# V2164MIXER_v2.net
KiCad netlist of a schematic drawn in EAGLE
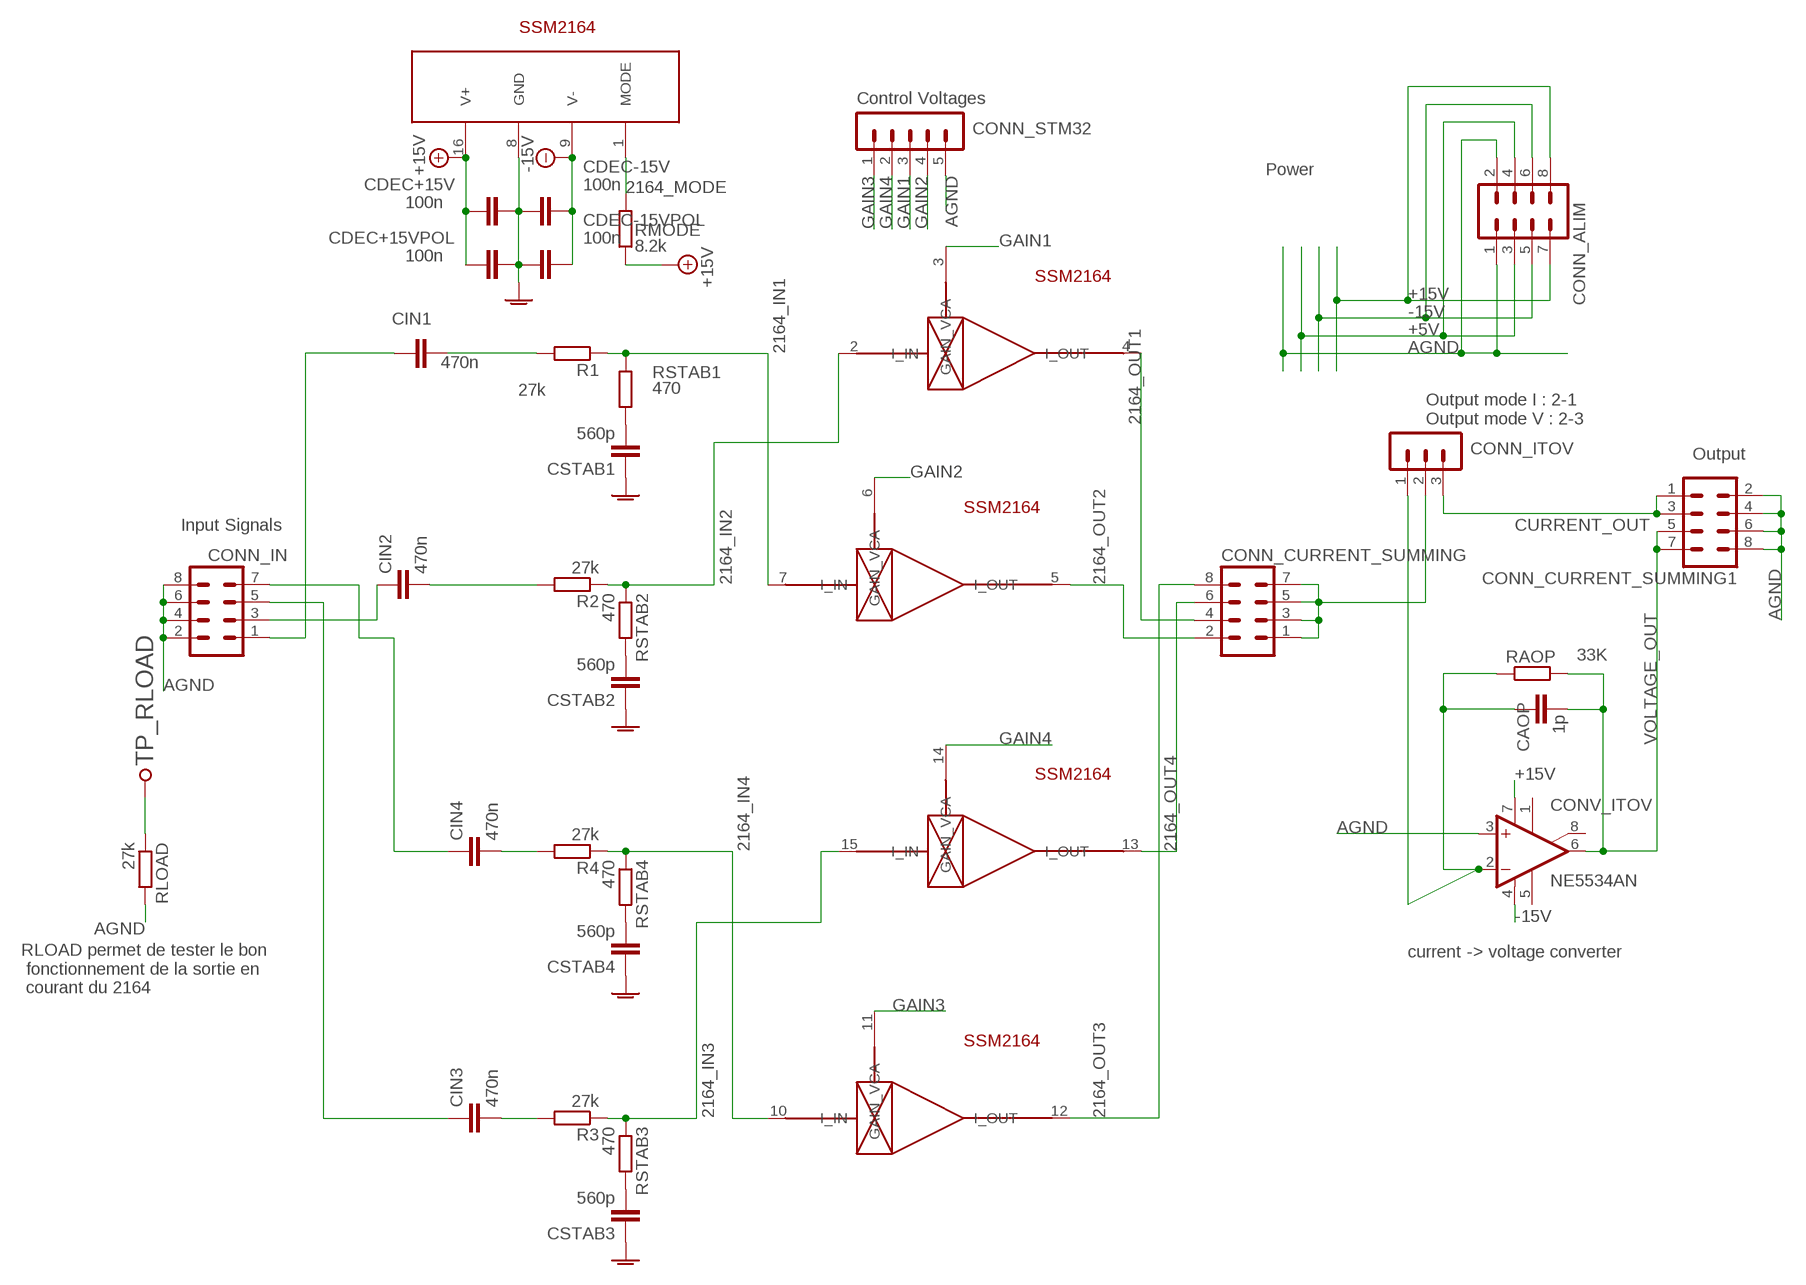
[diagram p0: schematic, sheet 1]

(export (version "E")
  (design (tool "Eeschema 10.0.6"))
  (components
    (comp (ref "CAOP")
      (value "1p")
      (footprint "eagle-import:C050-030X075")
      (fields (field (name "C3") "0.47 micro"))
      (libsource (lib "eagle-import") (part "C-EU050-030X075"))
    )
    (comp (ref "CDEC+15V")
      (value "100n")
      (footprint "eagle-import:C050-030X075")
      (libsource (lib "eagle-import") (part "C-EU050-030X075"))
    )
    (comp (ref "CDEC+15VPOL")
      (value "100n")
      (footprint "eagle-import:C075-032X103")
      (libsource (lib "eagle-import") (part "C-EU075-032X103"))
    )
    (comp (ref "CDEC-15V")
      (value "100n")
      (footprint "eagle-import:C050-030X075")
      (libsource (lib "eagle-import") (part "C-EU050-030X075"))
    )
    (comp (ref "CDEC-15VPOL")
      (value "100n")
      (footprint "eagle-import:C050-030X075")
      (libsource (lib "eagle-import") (part "C-EU050-030X075"))
    )
    (comp (ref "CIN1")
      (value "470n")
      (footprint "eagle-import:C050-030X075")
      (fields (field (name "C3") "0.47 micro"))
      (libsource (lib "eagle-import") (part "C-EU050-030X075"))
    )
    (comp (ref "CIN2")
      (value "470n")
      (footprint "eagle-import:C050-030X075")
      (fields (field (name "C3") "0.47 micro"))
      (libsource (lib "eagle-import") (part "C-EU050-030X075"))
    )
    (comp (ref "CIN3")
      (value "470n")
      (footprint "eagle-import:C050-030X075")
      (fields (field (name "C3") "0.47 micro"))
      (libsource (lib "eagle-import") (part "C-EU050-030X075"))
    )
    (comp (ref "CIN4")
      (value "470n")
      (footprint "eagle-import:C050-030X075")
      (fields (field (name "C3") "0.47 micro"))
      (libsource (lib "eagle-import") (part "C-EU050-030X075"))
    )
    (comp (ref "CONN_ALIM")
      (value "MA04-2")
      (footprint "eagle-import:MA04-2")
      (libsource (lib "eagle-import") (part "MA04-2"))
    )
    (comp (ref "CONN_CURRENT_SUMMING")
      (value "MA04-2")
      (footprint "eagle-import:MA04-2")
      (libsource (lib "eagle-import") (part "MA04-2"))
    )
    (comp (ref "CONN_CURRENT_SUMMING1")
      (value "MA04-2")
      (footprint "eagle-import:MA04-2")
      (libsource (lib "eagle-import") (part "MA04-2"))
    )
    (comp (ref "CONN_IN")
      (value "MA04-2")
      (footprint "eagle-import:MA04-2")
      (libsource (lib "eagle-import") (part "MA04-2"))
    )
    (comp (ref "CONN_ITOV")
      (value "MA03-1")
      (footprint "eagle-import:MA03-1")
      (libsource (lib "eagle-import") (part "MA03-1"))
    )
    (comp (ref "CONN_STM32")
      (value "MA05-1")
      (footprint "eagle-import:MA05-1")
      (libsource (lib "eagle-import") (part "MA05-1"))
    )
    (comp (ref "CONV_ITOV")
      (value "NE5534AN")
      (footprint "eagle-import:DIL08")
      (libsource (lib "eagle-import") (part "NE5534NA"))
    )
    (comp (ref "CSTAB1")
      (value "560p")
      (footprint "eagle-import:C050-030X075")
      (libsource (lib "eagle-import") (part "C-EU050-030X075"))
    )
    (comp (ref "CSTAB2")
      (value "560p")
      (footprint "eagle-import:C050-030X075")
      (libsource (lib "eagle-import") (part "C-EU050-030X075"))
    )
    (comp (ref "CSTAB3")
      (value "560p")
      (footprint "eagle-import:C050-030X075")
      (libsource (lib "eagle-import") (part "C-EU050-030X075"))
    )
    (comp (ref "CSTAB4")
      (value "560p")
      (footprint "eagle-import:C050-030X075")
      (libsource (lib "eagle-import") (part "C-EU050-030X075"))
    )
    (comp (ref "MIXER")
      (value "SSM2164_MULTI")
      (footprint "eagle-import:DIL16")
      (libsource (lib "eagle-import") (part "SSM2164_MULTI"))
    )
    (comp (ref "R1")
      (value "27k")
      (footprint "eagle-import:0207_10")
      (libsource (lib "eagle-import") (part "R-EU_0207/10"))
    )
    (comp (ref "R2")
      (value "27k")
      (footprint "eagle-import:0204_7")
      (libsource (lib "eagle-import") (part "R-EU_0204/7"))
    )
    (comp (ref "R3")
      (value "27k")
      (footprint "eagle-import:0204_7")
      (libsource (lib "eagle-import") (part "R-EU_0204/7"))
    )
    (comp (ref "R4")
      (value "27k")
      (footprint "eagle-import:0204_7")
      (libsource (lib "eagle-import") (part "R-EU_0204/7"))
    )
    (comp (ref "RAOP")
      (value "33K")
      (footprint "eagle-import:0204_7")
      (libsource (lib "eagle-import") (part "R-EU_0204/7"))
    )
    (comp (ref "RLOAD")
      (value "27k")
      (footprint "eagle-import:0204_7")
      (libsource (lib "eagle-import") (part "R-EU_0204/7"))
    )
    (comp (ref "RMODE")
      (value "8.2k")
      (footprint "eagle-import:0204_7")
      (libsource (lib "eagle-import") (part "R-EU_0204/7"))
    )
    (comp (ref "RSTAB1")
      (value "470")
      (footprint "eagle-import:0207_10")
      (libsource (lib "eagle-import") (part "R-EU_0207/10"))
    )
    (comp (ref "RSTAB2")
      (value "470")
      (footprint "eagle-import:0204_7")
      (libsource (lib "eagle-import") (part "R-EU_0204/7"))
    )
    (comp (ref "RSTAB3")
      (value "470")
      (footprint "eagle-import:0204_7")
      (libsource (lib "eagle-import") (part "R-EU_0204/7"))
    )
    (comp (ref "RSTAB4")
      (value "470")
      (footprint "eagle-import:0204_7")
      (libsource (lib "eagle-import") (part "R-EU_0204/7"))
    )
    (comp (ref "TP_RLOAD")
      (value "TESTPOINT")
      (footprint "eagle-import:TESTPOINT_63")
      (libsource (lib "eagle-import") (part "TESTPOINT"))
    )
  )
  (nets
    (net (code "1") (name "+15V") (class "Default")
      (node (ref "CDEC+15V") (pin "2") (pinfunction "2_2") (pintype "passive"))
      (node (ref "CDEC+15VPOL") (pin "2") (pinfunction "2_2") (pintype "passive"))
      (node (ref "CONN_ALIM") (pin "7") (pinfunction "7_7") (pintype "passive"))
      (node (ref "CONN_ALIM") (pin "8") (pinfunction "8_8") (pintype "passive"))
      (node (ref "CONV_ITOV") (pin "7") (pinfunction "V+_7") (pintype "power_in"))
      (node (ref "MIXER") (pin "16") (pinfunction "V+_16") (pintype "bidirectional"))
      (node (ref "RMODE") (pin "1") (pinfunction "1_1") (pintype "passive"))
    )
    (net (code "2") (name "-15V") (class "Default")
      (node (ref "CDEC-15V") (pin "1") (pinfunction "1_1") (pintype "passive"))
      (node (ref "CDEC-15VPOL") (pin "1") (pinfunction "1_1") (pintype "passive"))
      (node (ref "CONN_ALIM") (pin "5") (pinfunction "5_5") (pintype "passive"))
      (node (ref "CONN_ALIM") (pin "6") (pinfunction "6_6") (pintype "passive"))
      (node (ref "CONV_ITOV") (pin "4") (pinfunction "V-_4") (pintype "power_in"))
      (node (ref "MIXER") (pin "9") (pinfunction "V-_9") (pintype "bidirectional"))
    )
    (net (code "3") (name "/+5V") (class "Default")
      (node (ref "CONN_ALIM") (pin "3") (pinfunction "3_3") (pintype "passive"))
      (node (ref "CONN_ALIM") (pin "4") (pinfunction "4_4") (pintype "passive"))
    )
    (net (code "4") (name "/2164_IN1") (class "Default")
      (node (ref "MIXER") (pin "7") (pinfunction "I_IN_7") (pintype "bidirectional"))
      (node (ref "R1") (pin "1") (pinfunction "1_1") (pintype "passive"))
      (node (ref "RSTAB1") (pin "1") (pinfunction "1_1") (pintype "passive"))
    )
    (net (code "5") (name "/2164_IN2") (class "Default")
      (node (ref "MIXER") (pin "2") (pinfunction "I_IN_2") (pintype "bidirectional"))
      (node (ref "R2") (pin "1") (pinfunction "1_1") (pintype "passive"))
      (node (ref "RSTAB2") (pin "1") (pinfunction "1_1") (pintype "passive"))
    )
    (net (code "6") (name "/2164_IN3") (class "Default")
      (node (ref "MIXER") (pin "15") (pinfunction "I_IN_15") (pintype "bidirectional"))
      (node (ref "R3") (pin "1") (pinfunction "1_1") (pintype "passive"))
      (node (ref "RSTAB3") (pin "1") (pinfunction "1_1") (pintype "passive"))
    )
    (net (code "7") (name "/2164_IN4") (class "Default")
      (node (ref "MIXER") (pin "10") (pinfunction "I_IN_10") (pintype "bidirectional"))
      (node (ref "R4") (pin "1") (pinfunction "1_1") (pintype "passive"))
      (node (ref "RSTAB4") (pin "1") (pinfunction "1_1") (pintype "passive"))
    )
    (net (code "8") (name "/2164_MODE") (class "Default")
      (node (ref "MIXER") (pin "1") (pinfunction "MODE_1") (pintype "bidirectional"))
      (node (ref "RMODE") (pin "2") (pinfunction "2_2") (pintype "passive"))
    )
    (net (code "9") (name "/2164_OUT1") (class "Default")
      (node (ref "CONN_CURRENT_SUMMING") (pin "4") (pinfunction "4_4") (pintype "passive"))
      (node (ref "MIXER") (pin "4") (pinfunction "I_OUT_4") (pintype "bidirectional"))
    )
    (net (code "10") (name "/2164_OUT2") (class "Default")
      (node (ref "CONN_CURRENT_SUMMING") (pin "2") (pinfunction "2_2") (pintype "passive"))
      (node (ref "MIXER") (pin "5") (pinfunction "I_OUT_5") (pintype "bidirectional"))
    )
    (net (code "11") (name "/2164_OUT3") (class "Default")
      (node (ref "CONN_CURRENT_SUMMING") (pin "8") (pinfunction "8_8") (pintype "passive"))
      (node (ref "MIXER") (pin "12") (pinfunction "I_OUT_12") (pintype "bidirectional"))
    )
    (net (code "12") (name "/2164_OUT4") (class "Default")
      (node (ref "CONN_CURRENT_SUMMING") (pin "6") (pinfunction "6_6") (pintype "passive"))
      (node (ref "MIXER") (pin "13") (pinfunction "I_OUT_13") (pintype "bidirectional"))
    )
    (net (code "13") (name "/CURRENT_OUT") (class "Default")
      (node (ref "CONN_CURRENT_SUMMING1") (pin "1") (pinfunction "1_1") (pintype "passive"))
      (node (ref "CONN_CURRENT_SUMMING1") (pin "3") (pinfunction "3_3") (pintype "passive"))
      (node (ref "CONN_ITOV") (pin "3") (pinfunction "3_3") (pintype "passive"))
    )
    (net (code "14") (name "/GAIN1") (class "Default")
      (node (ref "CONN_STM32") (pin "3") (pinfunction "3_3") (pintype "passive"))
      (node (ref "MIXER") (pin "3") (pinfunction "GAIN_VCA_3") (pintype "bidirectional"))
    )
    (net (code "15") (name "/GAIN2") (class "Default")
      (node (ref "CONN_STM32") (pin "4") (pinfunction "4_4") (pintype "passive"))
      (node (ref "MIXER") (pin "6") (pinfunction "GAIN_VCA_6") (pintype "bidirectional"))
    )
    (net (code "16") (name "/GAIN3") (class "Default")
      (node (ref "CONN_STM32") (pin "1") (pinfunction "1_1") (pintype "passive"))
      (node (ref "MIXER") (pin "11") (pinfunction "GAIN_VCA_11") (pintype "bidirectional"))
    )
    (net (code "17") (name "/GAIN4") (class "Default")
      (node (ref "CONN_STM32") (pin "2") (pinfunction "2_2") (pintype "passive"))
      (node (ref "MIXER") (pin "14") (pinfunction "GAIN_VCA_14") (pintype "bidirectional"))
    )
    (net (code "18") (name "/VOLTAGE_OUT") (class "Default")
      (node (ref "CAOP") (pin "2") (pinfunction "2_2") (pintype "passive"))
      (node (ref "CONN_CURRENT_SUMMING1") (pin "5") (pinfunction "5_5") (pintype "passive"))
      (node (ref "CONN_CURRENT_SUMMING1") (pin "7") (pinfunction "7_7") (pintype "passive"))
      (node (ref "CONV_ITOV") (pin "6") (pinfunction "OUT_6") (pintype "output"))
      (node (ref "RAOP") (pin "2") (pinfunction "2_2") (pintype "passive"))
    )
    (net (code "19") (name "AGND") (class "Default")
      (node (ref "CDEC+15V") (pin "1") (pinfunction "1_1") (pintype "passive"))
      (node (ref "CDEC+15VPOL") (pin "1") (pinfunction "1_1") (pintype "passive"))
      (node (ref "CDEC-15V") (pin "2") (pinfunction "2_2") (pintype "passive"))
      (node (ref "CDEC-15VPOL") (pin "2") (pinfunction "2_2") (pintype "passive"))
      (node (ref "CONN_ALIM") (pin "1") (pinfunction "1_1") (pintype "passive"))
      (node (ref "CONN_ALIM") (pin "2") (pinfunction "2_2") (pintype "passive"))
      (node (ref "CONN_CURRENT_SUMMING1") (pin "2") (pinfunction "2_2") (pintype "passive"))
      (node (ref "CONN_CURRENT_SUMMING1") (pin "4") (pinfunction "4_4") (pintype "passive"))
      (node (ref "CONN_CURRENT_SUMMING1") (pin "6") (pinfunction "6_6") (pintype "passive"))
      (node (ref "CONN_CURRENT_SUMMING1") (pin "8") (pinfunction "8_8") (pintype "passive"))
      (node (ref "CONN_IN") (pin "2") (pinfunction "2_2") (pintype "passive"))
      (node (ref "CONN_IN") (pin "4") (pinfunction "4_4") (pintype "passive"))
      (node (ref "CONN_IN") (pin "6") (pinfunction "6_6") (pintype "passive"))
      (node (ref "CONN_IN") (pin "8") (pinfunction "8_8") (pintype "passive"))
      (node (ref "CONN_STM32") (pin "5") (pinfunction "5_5") (pintype "passive"))
      (node (ref "CONV_ITOV") (pin "3") (pinfunction "+IN_3") (pintype "input"))
      (node (ref "CSTAB1") (pin "1") (pinfunction "1_1") (pintype "passive"))
      (node (ref "CSTAB2") (pin "1") (pinfunction "1_1") (pintype "passive"))
      (node (ref "CSTAB3") (pin "1") (pinfunction "1_1") (pintype "passive"))
      (node (ref "CSTAB4") (pin "1") (pinfunction "1_1") (pintype "passive"))
      (node (ref "MIXER") (pin "8") (pinfunction "GND_8") (pintype "bidirectional"))
      (node (ref "RLOAD") (pin "2") (pinfunction "2_2") (pintype "passive"))
    )
    (net (code "20") (name "Net-(CIN1-Pad1)") (class "Default")
      (node (ref "CIN1") (pin "1") (pinfunction "1_1") (pintype "passive"))
      (node (ref "CONN_IN") (pin "1") (pinfunction "1_1") (pintype "passive"))
    )
    (net (code "21") (name "Net-(CIN1-Pad2)") (class "Default")
      (node (ref "CIN1") (pin "2") (pinfunction "2_2") (pintype "passive"))
      (node (ref "R1") (pin "2") (pinfunction "2_2") (pintype "passive"))
    )
    (net (code "22") (name "Net-(CIN2-Pad1)") (class "Default")
      (node (ref "CIN2") (pin "1") (pinfunction "1_1") (pintype "passive"))
      (node (ref "CONN_IN") (pin "3") (pinfunction "3_3") (pintype "passive"))
    )
    (net (code "23") (name "Net-(CIN2-Pad2)") (class "Default")
      (node (ref "CIN2") (pin "2") (pinfunction "2_2") (pintype "passive"))
      (node (ref "R2") (pin "2") (pinfunction "2_2") (pintype "passive"))
    )
    (net (code "24") (name "Net-(CIN3-Pad1)") (class "Default")
      (node (ref "CIN3") (pin "1") (pinfunction "1_1") (pintype "passive"))
      (node (ref "CONN_IN") (pin "5") (pinfunction "5_5") (pintype "passive"))
    )
    (net (code "25") (name "Net-(CIN3-Pad2)") (class "Default")
      (node (ref "CIN3") (pin "2") (pinfunction "2_2") (pintype "passive"))
      (node (ref "R3") (pin "2") (pinfunction "2_2") (pintype "passive"))
    )
    (net (code "26") (name "Net-(CIN4-Pad1)") (class "Default")
      (node (ref "CIN4") (pin "1") (pinfunction "1_1") (pintype "passive"))
      (node (ref "CONN_IN") (pin "7") (pinfunction "7_7") (pintype "passive"))
    )
    (net (code "27") (name "Net-(CIN4-Pad2)") (class "Default")
      (node (ref "CIN4") (pin "2") (pinfunction "2_2") (pintype "passive"))
      (node (ref "R4") (pin "2") (pinfunction "2_2") (pintype "passive"))
    )
    (net (code "28") (name "Net-(CONN_CURRENT_SUMMING-Pad1)") (class "Default")
      (node (ref "CONN_CURRENT_SUMMING") (pin "1") (pinfunction "1_1") (pintype "passive"))
      (node (ref "CONN_CURRENT_SUMMING") (pin "3") (pinfunction "3_3") (pintype "passive"))
      (node (ref "CONN_CURRENT_SUMMING") (pin "5") (pinfunction "5_5") (pintype "passive"))
      (node (ref "CONN_CURRENT_SUMMING") (pin "7") (pinfunction "7_7") (pintype "passive"))
      (node (ref "CONN_ITOV") (pin "2") (pinfunction "2_2") (pintype "passive"))
    )
    (net (code "29") (name "Net-(CONV_ITOV--IN)") (class "Default")
      (node (ref "CAOP") (pin "1") (pinfunction "1_1") (pintype "passive"))
      (node (ref "CONN_ITOV") (pin "1") (pinfunction "1_1") (pintype "passive"))
      (node (ref "CONV_ITOV") (pin "2") (pinfunction "-IN_2") (pintype "input"))
      (node (ref "RAOP") (pin "1") (pinfunction "1_1") (pintype "passive"))
    )
    (net (code "30") (name "Net-(CSTAB1-Pad2)") (class "Default")
      (node (ref "CSTAB1") (pin "2") (pinfunction "2_2") (pintype "passive"))
      (node (ref "RSTAB1") (pin "2") (pinfunction "2_2") (pintype "passive"))
    )
    (net (code "31") (name "Net-(CSTAB2-Pad2)") (class "Default")
      (node (ref "CSTAB2") (pin "2") (pinfunction "2_2") (pintype "passive"))
      (node (ref "RSTAB2") (pin "2") (pinfunction "2_2") (pintype "passive"))
    )
    (net (code "32") (name "Net-(CSTAB3-Pad2)") (class "Default")
      (node (ref "CSTAB3") (pin "2") (pinfunction "2_2") (pintype "passive"))
      (node (ref "RSTAB3") (pin "2") (pinfunction "2_2") (pintype "passive"))
    )
    (net (code "33") (name "Net-(CSTAB4-Pad2)") (class "Default")
      (node (ref "CSTAB4") (pin "2") (pinfunction "2_2") (pintype "passive"))
      (node (ref "RSTAB4") (pin "2") (pinfunction "2_2") (pintype "passive"))
    )
    (net (code "34") (name "Net-(RLOAD-Pad1)") (class "Default")
      (node (ref "RLOAD") (pin "1") (pinfunction "1_1") (pintype "passive"))
      (node (ref "TP_RLOAD") (pin "P$1") (pinfunction "P$1_P$1") (pintype "passive"))
    )
    (net (code "35") (name "unconnected-(CONV_ITOV-CMP-Pad5)") (class "Default")
      (node (ref "CONV_ITOV") (pin "5") (pinfunction "CMP_5") (pintype "passive"))
    )
    (net (code "36") (name "unconnected-(CONV_ITOV-ON-Pad1)") (class "Default")
      (node (ref "CONV_ITOV") (pin "1") (pinfunction "ON_1") (pintype "passive"))
    )
    (net (code "37") (name "unconnected-(CONV_ITOV-ON{slash}CMP-Pad8)") (class "Default")
      (node (ref "CONV_ITOV") (pin "8") (pinfunction "ON/CMP_8") (pintype "passive"))
    )
  )
)
